# 2025_08_26_usb2uart.net
KiCad netlist of a schematic drawn in EasyEDA Pro
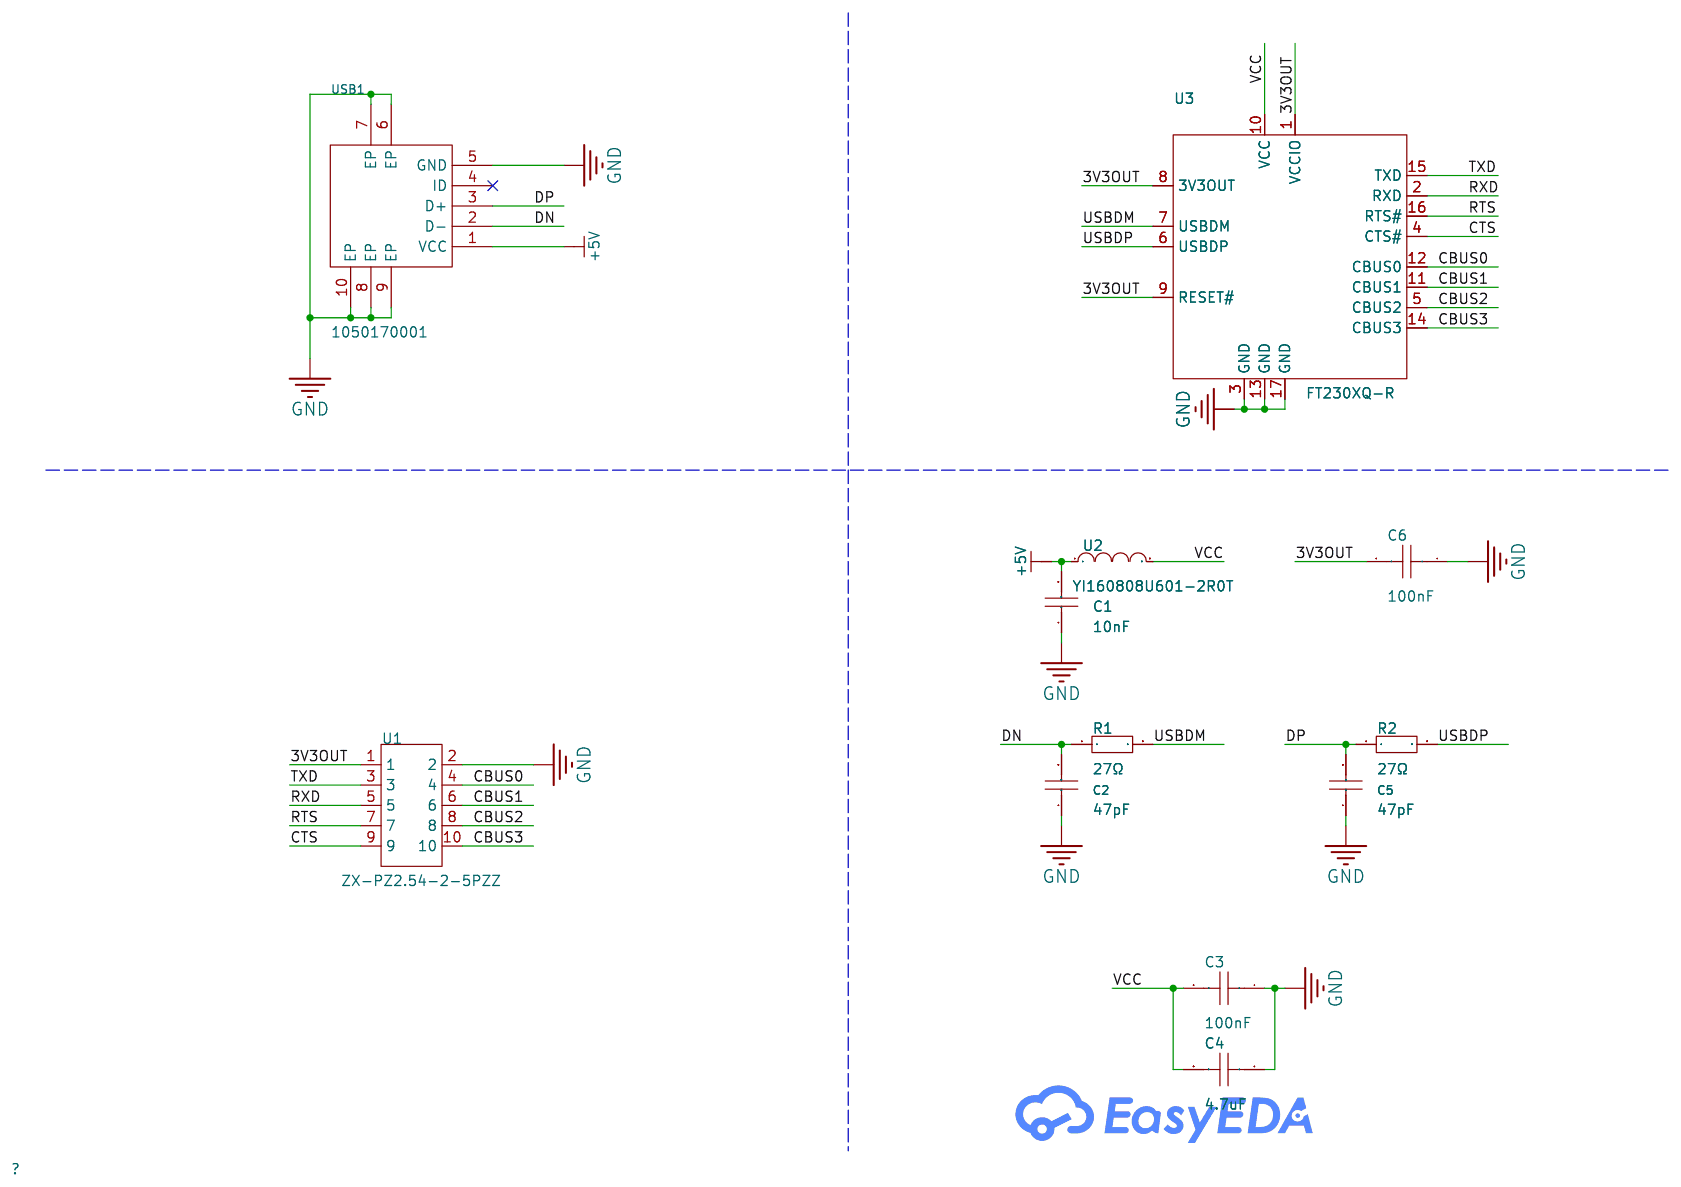
[diagram p0: schematic sheet]

(export (version "E")
  (design (tool "Eeschema 10.0.6"))
  (components
    (comp (ref "C1")
      (value "10nF")
      (footprint "easyedapro:C0402")
      (description "Capacitance:10nF Tolerance:±10% Tolerance:±10% Voltage Rating:50V Temperature Coefficient:X7R")
      (fields
        (field (name "Manufacturer Part") "CL05B103KB5NNNC")
        (field (name "Manufacturer") "SAMSUNG(三星)")
      )
      (libsource (lib "easyedapro") (part "CL05B103KB5NNNC"))
    )
    (comp (ref "C2")
      (value "47pF")
      (footprint "easyedapro:C0402")
      (fields
        (field (name "Manufacturer Part") "CC0402JRNPO9BN470")
        (field (name "Manufacturer") "YAGEO(国巨)")
      )
      (libsource (lib "easyedapro") (part "CC0402JRNPO9BN470"))
    )
    (comp (ref "C3")
      (value "100nF")
      (footprint "easyedapro:C0402")
      (fields
        (field (name "Manufacturer Part") "CL05B104KO5NNNC")
        (field (name "Manufacturer") "SAMSUNG(三星)")
      )
      (libsource (lib "easyedapro") (part "CL05B104KO5NNNC"))
    )
    (comp (ref "C4")
      (value "4.7uF")
      (footprint "easyedapro:C0402")
      (description "Capacitance:4.7uF Tolerance:±20% Tolerance:±20% Voltage Rating:6.3V Temperature Coefficient:X5R")
      (fields
        (field (name "Manufacturer Part") "CL05A475MQ5NRNC")
        (field (name "Manufacturer") "SAMSUNG(三星)")
      )
      (libsource (lib "easyedapro") (part "CL05A475MQ5NRNC_C307423"))
    )
    (comp (ref "C5")
      (value "47pF")
      (footprint "easyedapro:C0402")
      (fields
        (field (name "Manufacturer Part") "CC0402JRNPO9BN470")
        (field (name "Manufacturer") "YAGEO(国巨)")
      )
      (libsource (lib "easyedapro") (part "CC0402JRNPO9BN470"))
    )
    (comp (ref "C6")
      (value "100nF")
      (footprint "easyedapro:C0402")
      (fields
        (field (name "Manufacturer Part") "CL05B104KO5NNNC")
        (field (name "Manufacturer") "SAMSUNG(三星)")
      )
      (libsource (lib "easyedapro") (part "CL05B104KO5NNNC"))
    )
    (comp (ref "R1")
      (value "27Ω")
      (footprint "easyedapro:R0402")
      (fields (field (name "Manufacturer Part") "RC0402FR-0727RL") (field (name "Manufacturer") "YAGEO(国巨)"))
      (libsource (lib "easyedapro") (part "RC0402FR-0727RL"))
    )
    (comp (ref "R2")
      (value "27Ω")
      (footprint "easyedapro:R0402")
      (fields (field (name "Manufacturer Part") "RC0402FR-0727RL") (field (name "Manufacturer") "YAGEO(国巨)"))
      (libsource (lib "easyedapro") (part "RC0402FR-0727RL"))
    )
    (comp (ref "U1")
      (value "ZX-PZ2.54-2-5PZZ")
      (footprint "easyedapro:HDR-TH_10P-P2.54-V-M-R2-C5-S2.54")
      (fields (field (name "Manufacturer") "Megastar(兆星)"))
      (libsource (lib "easyedapro") (part "ZX-PZ2.54-2-5PZZ"))
    )
    (comp (ref "U2")
      (value "YI160808U601-2R0T")
      (footprint "easyedapro:L0603")
      (fields (field (name "Manufacturer") "YJYCOIN(益嘉源)"))
      (libsource (lib "easyedapro") (part "YI160808U601-2R0T"))
    )
    (comp (ref "U3")
      (value "FT230XQ-R")
      (footprint "easyedapro:QFN-16_L4.0-W4.0-P0.65-BL-EP2.2")
      (fields (field (name "Manufacturer") "FTDI(飞特帝亚)"))
      (libsource (lib "easyedapro") (part "FT230XQ-R"))
    )
    (comp (ref "USB1")
      (value "1050170001")
      (footprint "easyedapro:MICRO-USB-SMD_105017-0001")
      (fields (field (name "Manufacturer") "MOLEX"))
      (libsource (lib "easyedapro") (part "105017-0001"))
    )
  )
  (nets
    (net (code "1") (name "+5V") (class "Default")
      (node (ref "C1") (pin "2") (pinfunction "2_2") (pintype "input"))
      (node (ref "U2") (pin "1") (pinfunction "1_1") (pintype "unspecified"))
      (node (ref "USB1") (pin "1") (pinfunction "VCC_1") (pintype "input"))
    )
    (net (code "2") (name "/3V3OUT") (class "Default")
      (node (ref "C6") (pin "2") (pinfunction "2_2") (pintype "unspecified"))
      (node (ref "U1") (pin "1") (pinfunction "1_1") (pintype "unspecified"))
      (node (ref "U3") (pin "1") (pinfunction "VCCIO_1") (pintype "unspecified"))
      (node (ref "U3") (pin "8") (pinfunction "3V3OUT_8") (pintype "unspecified"))
      (node (ref "U3") (pin "9") (pinfunction "RESET#_9") (pintype "unspecified"))
    )
    (net (code "3") (name "/CBUS0") (class "Default")
      (node (ref "U1") (pin "4") (pinfunction "4_4") (pintype "unspecified"))
      (node (ref "U3") (pin "12") (pinfunction "CBUS0_12") (pintype "unspecified"))
    )
    (net (code "4") (name "/CBUS1") (class "Default")
      (node (ref "U1") (pin "6") (pinfunction "6_6") (pintype "unspecified"))
      (node (ref "U3") (pin "11") (pinfunction "CBUS1_11") (pintype "unspecified"))
    )
    (net (code "5") (name "/CBUS2") (class "Default")
      (node (ref "U1") (pin "8") (pinfunction "8_8") (pintype "unspecified"))
      (node (ref "U3") (pin "5") (pinfunction "CBUS2_5") (pintype "unspecified"))
    )
    (net (code "6") (name "/CBUS3") (class "Default")
      (node (ref "U1") (pin "10") (pinfunction "10_10") (pintype "unspecified"))
      (node (ref "U3") (pin "14") (pinfunction "CBUS3_14") (pintype "unspecified"))
    )
    (net (code "7") (name "/CTS") (class "Default")
      (node (ref "U1") (pin "9") (pinfunction "9_9") (pintype "unspecified"))
      (node (ref "U3") (pin "4") (pinfunction "CTS#_4") (pintype "unspecified"))
    )
    (net (code "8") (name "/DN") (class "Default")
      (node (ref "C2") (pin "2") (pinfunction "2_2") (pintype "input"))
      (node (ref "R1") (pin "1") (pinfunction "1_1") (pintype "input"))
      (node (ref "USB1") (pin "2") (pinfunction "D-_2") (pintype "input"))
    )
    (net (code "9") (name "/DP") (class "Default")
      (node (ref "C5") (pin "2") (pinfunction "2_2") (pintype "input"))
      (node (ref "R2") (pin "1") (pinfunction "1_1") (pintype "input"))
      (node (ref "USB1") (pin "3") (pinfunction "D+_3") (pintype "input"))
    )
    (net (code "10") (name "/RTS") (class "Default")
      (node (ref "U1") (pin "7") (pinfunction "7_7") (pintype "unspecified"))
      (node (ref "U3") (pin "16") (pinfunction "RTS#_16") (pintype "unspecified"))
    )
    (net (code "11") (name "/RXD") (class "Default")
      (node (ref "U1") (pin "5") (pinfunction "5_5") (pintype "unspecified"))
      (node (ref "U3") (pin "2") (pinfunction "RXD_2") (pintype "unspecified"))
    )
    (net (code "12") (name "/TXD") (class "Default")
      (node (ref "U1") (pin "3") (pinfunction "3_3") (pintype "unspecified"))
      (node (ref "U3") (pin "15") (pinfunction "TXD_15") (pintype "unspecified"))
    )
    (net (code "13") (name "/USBDM") (class "Default")
      (node (ref "R1") (pin "2") (pinfunction "2_2") (pintype "input"))
      (node (ref "U3") (pin "7") (pinfunction "USBDM_7") (pintype "unspecified"))
    )
    (net (code "14") (name "/USBDP") (class "Default")
      (node (ref "R2") (pin "2") (pinfunction "2_2") (pintype "input"))
      (node (ref "U3") (pin "6") (pinfunction "USBDP_6") (pintype "unspecified"))
    )
    (net (code "15") (name "/VCC") (class "Default")
      (node (ref "C3") (pin "2") (pinfunction "2_2") (pintype "unspecified"))
      (node (ref "C4") (pin "2") (pinfunction "2_2") (pintype "unspecified"))
      (node (ref "U2") (pin "2") (pinfunction "2_2") (pintype "unspecified"))
      (node (ref "U3") (pin "10") (pinfunction "VCC_10") (pintype "unspecified"))
    )
    (net (code "16") (name "GND") (class "Default")
      (node (ref "C1") (pin "1") (pinfunction "1_1") (pintype "input"))
      (node (ref "C2") (pin "1") (pinfunction "1_1") (pintype "input"))
      (node (ref "C3") (pin "1") (pinfunction "1_1") (pintype "unspecified"))
      (node (ref "C4") (pin "1") (pinfunction "1_1") (pintype "unspecified"))
      (node (ref "C5") (pin "1") (pinfunction "1_1") (pintype "input"))
      (node (ref "C6") (pin "1") (pinfunction "1_1") (pintype "unspecified"))
      (node (ref "U1") (pin "2") (pinfunction "2_2") (pintype "unspecified"))
      (node (ref "U3") (pin "13") (pinfunction "GND_13") (pintype "unspecified"))
      (node (ref "U3") (pin "17") (pinfunction "GND_17") (pintype "unspecified"))
      (node (ref "U3") (pin "3") (pinfunction "GND_3") (pintype "unspecified"))
      (node (ref "USB1") (pin "10") (pinfunction "EP_10") (pintype "input"))
      (node (ref "USB1") (pin "5") (pinfunction "GND_5") (pintype "input"))
      (node (ref "USB1") (pin "6") (pinfunction "EP_6") (pintype "input"))
      (node (ref "USB1") (pin "7") (pinfunction "EP_7") (pintype "input"))
      (node (ref "USB1") (pin "8") (pinfunction "EP_8") (pintype "input"))
      (node (ref "USB1") (pin "9") (pinfunction "EP_9") (pintype "input"))
    )
    (net (code "17") (name "unconnected-(USB1-ID-Pad4)") (class "Default")
      (node (ref "USB1") (pin "4") (pinfunction "ID_4") (pintype "input+no_connect"))
    )
  )
)
